# EMG_FSR.net
KiCad netlist of a schematic drawn in EAGLE
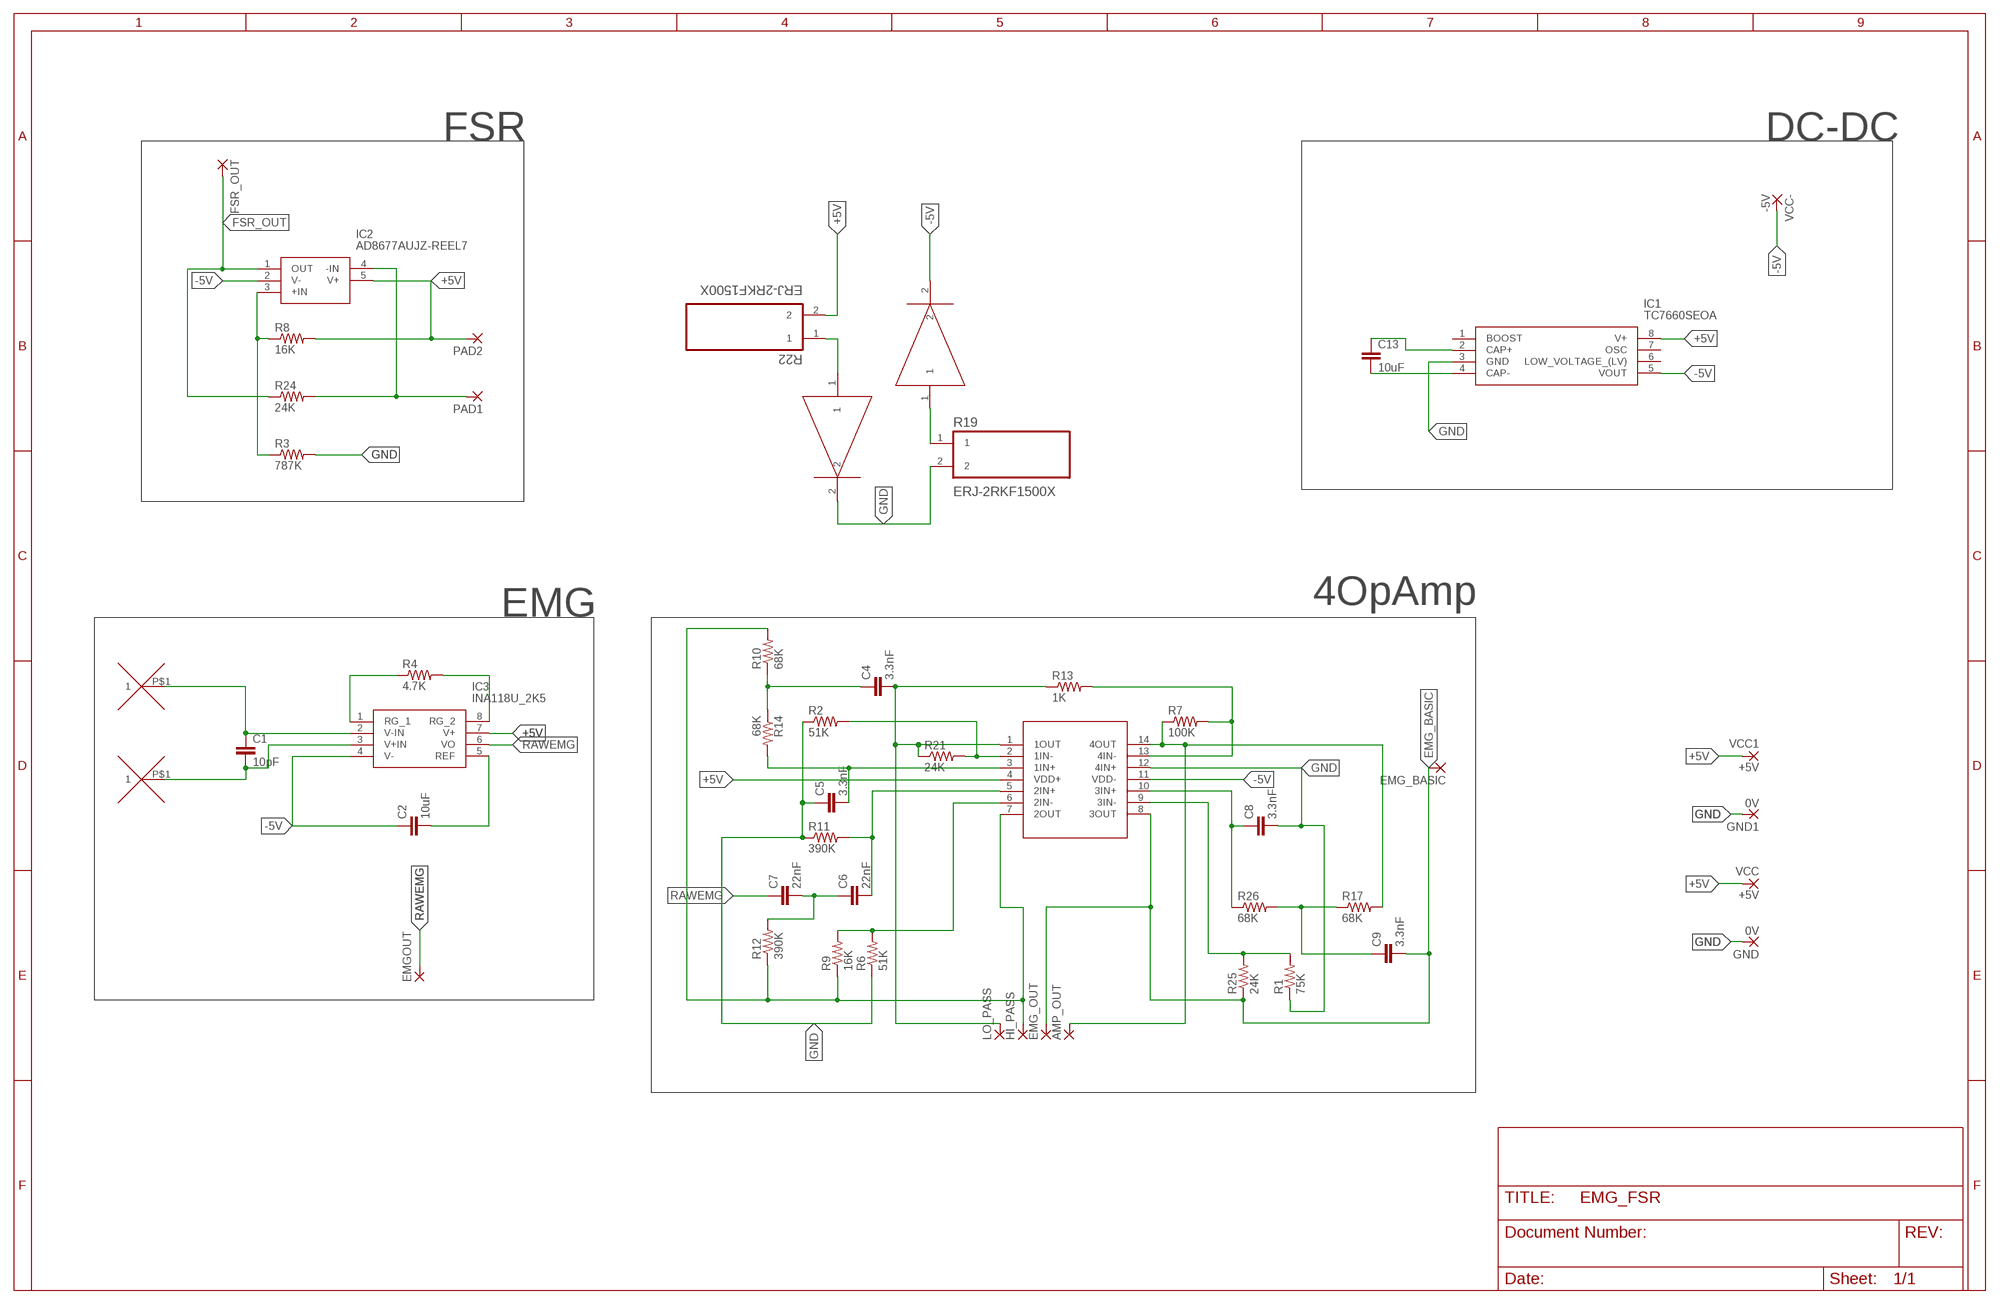
[diagram p0: schematic, sheet 1]

(export (version "E")
  (design (tool "Eeschema 10.0.6"))
  (components
    (comp (ref "AMP_OUT")
      (value "1,6/0,8")
      (footprint "eagle-import:1,6_0,8")
      (libsource (lib "eagle-import") (part "1,6/0,8"))
    )
    (comp (ref "C1")
      (value "10pF")
      (footprint "eagle-import:HPC0201")
      (libsource (lib "eagle-import") (part "rcl@1_C-EUHPC0201"))
    )
    (comp (ref "C2")
      (value "10uF")
      (footprint "eagle-import:C0805")
      (libsource (lib "eagle-import") (part "rcl@1_C-EUC0805"))
    )
    (comp (ref "C4")
      (value "3.3nF")
      (footprint "eagle-import:C1206")
      (libsource (lib "eagle-import") (part "C-EUC1206"))
    )
    (comp (ref "C5")
      (value "3.3nF")
      (footprint "eagle-import:C1206")
      (libsource (lib "eagle-import") (part "C-EUC1206"))
    )
    (comp (ref "C6")
      (value "22nF")
      (footprint "eagle-import:C0805")
      (libsource (lib "eagle-import") (part "C-EUC0805"))
    )
    (comp (ref "C7")
      (value "22nF")
      (footprint "eagle-import:C0805")
      (libsource (lib "eagle-import") (part "C-EUC0805"))
    )
    (comp (ref "C8")
      (value "3.3nF")
      (footprint "eagle-import:C1206")
      (libsource (lib "eagle-import") (part "C-EUC1206"))
    )
    (comp (ref "C9")
      (value "3.3nF")
      (footprint "eagle-import:C1206")
      (libsource (lib "eagle-import") (part "C-EUC1206"))
    )
    (comp (ref "C13")
      (value "10uF")
      (footprint "eagle-import:C0805K")
      (libsource (lib "eagle-import") (part "rcl@1_C-EUC0805K"))
    )
    (comp (ref "EMGOUT")
      (value "1,6/0,8")
      (footprint "eagle-import:1,6_0,8")
      (libsource (lib "eagle-import") (part "1,6/0,8"))
    )
    (comp (ref "EMG_BASIC")
      (value "1,6/0,8")
      (footprint "eagle-import:1,6_0,8")
      (libsource (lib "eagle-import") (part "1,6/0,8"))
    )
    (comp (ref "EMG_OUT")
      (value "1,6/0,8")
      (footprint "eagle-import:1,6_0,8")
      (libsource (lib "eagle-import") (part "1,6/0,8"))
    )
    (comp (ref "FSR_OUT")
      (value "1,6/0,8")
      (footprint "eagle-import:1,6_0,8")
      (libsource (lib "eagle-import") (part "1,6/0,8"))
    )
    (comp (ref "GND")
      (value "0V")
      (footprint "eagle-import:1,6_0,8")
      (libsource (lib "eagle-import") (part "1,6/0,8"))
    )
    (comp (ref "GND1")
      (value "0V")
      (footprint "eagle-import:1,6_0,8")
      (libsource (lib "eagle-import") (part "1,6/0,8"))
    )
    (comp (ref "HI_PASS")
      (value "1,6/0,8")
      (footprint "eagle-import:1,6_0,8")
      (libsource (lib "eagle-import") (part "1,6/0,8"))
    )
    (comp (ref "IC1")
      (value "TC7660SEOA")
      (footprint "eagle-import:SOIC127P600X175-8N")
      (fields (field (name "MOUSER_PART_NUMBER") "579-TC7660SEOA"))
      (libsource (lib "eagle-import") (part "TC7660SEOA"))
    )
    (comp (ref "IC2")
      (value "AD8677AUJZ-REEL7")
      (footprint "eagle-import:SOT95P280X100-5N")
      (fields (field (name "MOUSER_PART_NUMBER") "584-AD8677AUJZ-R7"))
      (libsource (lib "eagle-import") (part "AD8677AUJZ-REEL7"))
    )
    (comp (ref "IC3")
      (value "INA118U_2K5")
      (footprint "eagle-import:SOIC127P600X175-8N")
      (fields
        (field (name "ARROW_PART_NUMBER") "INA118U/2K5")
        (field (name "MOUSER_PART_NUMBER") "595-INA118U/2K5")
      )
      (libsource (lib "eagle-import") (part "INA118U_2K5"))
    )
    (comp (ref "LO_PASS")
      (value "1,6/0,8")
      (footprint "eagle-import:1,6_0,8")
      (libsource (lib "eagle-import") (part "1,6/0,8"))
    )
    (comp (ref "PAD1")
      (value "SMD2")
      (footprint "eagle-import:SMD1,27-2,54")
      (libsource (lib "eagle-import") (part "SMD2"))
    )
    (comp (ref "PAD2")
      (value "SMD2")
      (footprint "eagle-import:SMD1,27-2,54")
      (libsource (lib "eagle-import") (part "SMD2"))
    )
    (comp (ref "R1")
      (value "75K")
      (footprint "eagle-import:R0402")
      (libsource (lib "eagle-import") (part "adafruit@2_R-US_R0402"))
    )
    (comp (ref "R2")
      (value "51K")
      (footprint "eagle-import:R0402")
      (libsource (lib "eagle-import") (part "adafruit@2_R-US_R0402"))
    )
    (comp (ref "R3")
      (value "787K")
      (footprint "eagle-import:R0805")
      (libsource (lib "eagle-import") (part "rcl_R-US_R0805"))
    )
    (comp (ref "R4")
      (value "4.7K")
      (footprint "eagle-import:R0402")
      (libsource (lib "eagle-import") (part "adafruit@1_R-US_R0402"))
    )
    (comp (ref "R6")
      (value "51K")
      (footprint "eagle-import:R0402")
      (libsource (lib "eagle-import") (part "adafruit@2_R-US_R0402"))
    )
    (comp (ref "R7")
      (value "100K")
      (footprint "eagle-import:R1005")
      (libsource (lib "eagle-import") (part "adafruit@1_R-US_R1005"))
    )
    (comp (ref "R8")
      (value "16K")
      (footprint "eagle-import:R0402")
      (libsource (lib "eagle-import") (part "adafruit@2_R-US_R0402"))
    )
    (comp (ref "R9")
      (value "16K")
      (footprint "eagle-import:R0402")
      (libsource (lib "eagle-import") (part "adafruit@2_R-US_R0402"))
    )
    (comp (ref "R10")
      (value "68K")
      (footprint "eagle-import:R0402")
      (libsource (lib "eagle-import") (part "adafruit@2_R-US_R0402"))
    )
    (comp (ref "R11")
      (value "390K")
      (footprint "eagle-import:R0603")
      (libsource (lib "eagle-import") (part "R-US_R0603"))
    )
    (comp (ref "R12")
      (value "390K")
      (footprint "eagle-import:R0603")
      (libsource (lib "eagle-import") (part "adafruit@1_R-US_R0603"))
    )
    (comp (ref "R13")
      (value "1K")
      (footprint "eagle-import:R0402")
      (libsource (lib "eagle-import") (part "adafruit@2_R-US_R0402"))
    )
    (comp (ref "R14")
      (value "68K")
      (footprint "eagle-import:R0402")
      (libsource (lib "eagle-import") (part "adafruit@2_R-US_R0402"))
    )
    (comp (ref "R17")
      (value "68K")
      (footprint "eagle-import:R0402")
      (libsource (lib "eagle-import") (part "adafruit@2_R-US_R0402"))
    )
    (comp (ref "R19")
      (value "ERJ-2RKF1500X")
      (footprint "eagle-import:RESC1005X40N")
      (fields (field (name "DIGI-KEY_PART_NUMBER") "P150LCT-ND") (field (name "MF") "Panasonic Electronic"))
      (libsource (lib "eagle-import") (part "ERJ-2RKF1500X"))
    )
    (comp (ref "R20")
      (value "RESC0402X40N")
      (footprint "eagle-import:RESC0402X40N")
      (fields (field (name "MANUFACTURER") "KOA"))
      (libsource (lib "eagle-import") (part "RESC0402X40N"))
    )
    (comp (ref "R21")
      (value "24K")
      (footprint "eagle-import:R0402")
      (libsource (lib "eagle-import") (part "adafruit@2_R-US_R0402"))
    )
    (comp (ref "R22")
      (value "ERJ-2RKF1500X")
      (footprint "eagle-import:RESC1005X40N")
      (fields (field (name "DIGI-KEY_PART_NUMBER") "P150LCT-ND") (field (name "MF") "Panasonic Electronic"))
      (libsource (lib "eagle-import") (part "ERJ-2RKF1500X"))
    )
    (comp (ref "R24")
      (value "24K")
      (footprint "eagle-import:R0402")
      (libsource (lib "eagle-import") (part "adafruit@2_R-US_R0402"))
    )
    (comp (ref "R25")
      (value "24K")
      (footprint "eagle-import:R0402")
      (libsource (lib "eagle-import") (part "adafruit@2_R-US_R0402"))
    )
    (comp (ref "R26")
      (value "68K")
      (footprint "eagle-import:R0402")
      (libsource (lib "eagle-import") (part "adafruit@2_R-US_R0402"))
    )
    (comp (ref "RED")
      (value "RESC0402X40N")
      (footprint "eagle-import:RESC0402X40N")
      (fields (field (name "MANUFACTURER") "KOA"))
      (libsource (lib "eagle-import") (part "RESC0402X40N"))
    )
    (comp (ref "U$1")
      (value "TLC2274-HT")
      (footprint "eagle-import:SOP65P640X120-14N")
      (libsource (lib "eagle-import") (part "TLC2274-HT"))
    )
    (comp (ref "U$2")
      (value "EMG_VIA")
      (footprint "eagle-import:EMG_VIA")
      (libsource (lib "eagle-import") (part "EMG_VIA"))
    )
    (comp (ref "U$3")
      (value "EMG_VIA")
      (footprint "eagle-import:EMG_VIA")
      (libsource (lib "eagle-import") (part "EMG_VIA"))
    )
    (comp (ref "VCC")
      (value "+5V")
      (footprint "eagle-import:1,6_0,8")
      (libsource (lib "eagle-import") (part "1,6/0,8"))
    )
    (comp (ref "VCC-")
      (value "-5V")
      (footprint "eagle-import:1,6_0,8")
      (libsource (lib "eagle-import") (part "1,6/0,8"))
    )
    (comp (ref "VCC1")
      (value "+5V")
      (footprint "eagle-import:1,6_0,8")
      (libsource (lib "eagle-import") (part "1,6/0,8"))
    )
  )
  (nets
    (net (code "1") (name "+5V") (class "Default")
      (node (ref "IC1") (pin "8") (pinfunction "V+_8") (pintype "bidirectional"))
      (node (ref "IC2") (pin "5") (pinfunction "V+_5") (pintype "bidirectional"))
      (node (ref "IC3") (pin "7") (pinfunction "V+_7") (pintype "bidirectional"))
      (node (ref "PAD2") (pin "1") (pinfunction "P_1") (pintype "passive"))
      (node (ref "R22") (pin "2") (pinfunction "2_2") (pintype "bidirectional"))
      (node (ref "R8") (pin "2") (pinfunction "2_2") (pintype "passive"))
      (node (ref "U$1") (pin "4") (pinfunction "VDD+_4") (pintype "bidirectional"))
      (node (ref "VCC") (pin "1") (pinfunction "P_1") (pintype "passive"))
      (node (ref "VCC1") (pin "1") (pinfunction "P_1") (pintype "passive"))
    )
    (net (code "2") (name "-5V") (class "Default")
      (node (ref "C2") (pin "1") (pinfunction "1_1") (pintype "passive"))
      (node (ref "IC1") (pin "5") (pinfunction "VOUT_5") (pintype "bidirectional"))
      (node (ref "IC2") (pin "2") (pinfunction "V-_2") (pintype "bidirectional"))
      (node (ref "IC3") (pin "4") (pinfunction "V-_4") (pintype "bidirectional"))
      (node (ref "R20") (pin "2") (pinfunction "2_2") (pintype "bidirectional"))
      (node (ref "U$1") (pin "11") (pinfunction "VDD-_11") (pintype "bidirectional"))
      (node (ref "VCC-") (pin "1") (pinfunction "P_1") (pintype "passive"))
    )
    (net (code "3") (name "EMG_BASIC") (class "Default")
      (node (ref "C9") (pin "2") (pinfunction "2_2") (pintype "passive"))
      (node (ref "EMG_BASIC") (pin "1") (pinfunction "P_1") (pintype "passive"))
      (node (ref "EMG_OUT") (pin "1") (pinfunction "P_1") (pintype "passive"))
      (node (ref "R25") (pin "1") (pinfunction "1_1") (pintype "passive"))
      (node (ref "U$1") (pin "8") (pinfunction "3OUT_8") (pintype "bidirectional"))
    )
    (net (code "4") (name "FSR_OUT") (class "Default")
      (node (ref "FSR_OUT") (pin "1") (pinfunction "P_1") (pintype "passive"))
      (node (ref "IC2") (pin "1") (pinfunction "OUT_1") (pintype "output"))
      (node (ref "R24") (pin "1") (pinfunction "1_1") (pintype "passive"))
    )
    (net (code "5") (name "GND") (class "Default")
      (node (ref "C5") (pin "1") (pinfunction "1_1") (pintype "passive"))
      (node (ref "C8") (pin "2") (pinfunction "2_2") (pintype "passive"))
      (node (ref "GND") (pin "1") (pinfunction "P_1") (pintype "passive"))
      (node (ref "GND1") (pin "1") (pinfunction "P_1") (pintype "passive"))
      (node (ref "IC1") (pin "3") (pinfunction "GND_3") (pintype "bidirectional"))
      (node (ref "R1") (pin "1") (pinfunction "1_1") (pintype "passive"))
      (node (ref "R11") (pin "1") (pinfunction "1_1") (pintype "passive"))
      (node (ref "R19") (pin "2") (pinfunction "2_2") (pintype "bidirectional"))
      (node (ref "R2") (pin "1") (pinfunction "1_1") (pintype "passive"))
      (node (ref "R3") (pin "2") (pinfunction "2_2") (pintype "passive"))
      (node (ref "R6") (pin "1") (pinfunction "1_1") (pintype "passive"))
      (node (ref "RED") (pin "2") (pinfunction "2_2") (pintype "bidirectional"))
      (node (ref "U$1") (pin "12") (pinfunction "4IN+_12") (pintype "bidirectional"))
    )
    (net (code "6") (name "Net-(AMP_OUT-P)") (class "Default")
      (node (ref "AMP_OUT") (pin "1") (pinfunction "P_1") (pintype "passive"))
      (node (ref "R17") (pin "2") (pinfunction "2_2") (pintype "passive"))
      (node (ref "R7") (pin "1") (pinfunction "1_1") (pintype "passive"))
      (node (ref "U$1") (pin "14") (pinfunction "4OUT_14") (pintype "bidirectional"))
    )
    (net (code "7") (name "Net-(C4-Pad1)") (class "Default")
      (node (ref "C4") (pin "1") (pinfunction "1_1") (pintype "passive"))
      (node (ref "R10") (pin "1") (pinfunction "1_1") (pintype "passive"))
      (node (ref "R14") (pin "1") (pinfunction "1_1") (pintype "passive"))
    )
    (net (code "8") (name "Net-(C6-Pad1)") (class "Default")
      (node (ref "C6") (pin "1") (pinfunction "1_1") (pintype "passive"))
      (node (ref "C7") (pin "2") (pinfunction "2_2") (pintype "passive"))
      (node (ref "R12") (pin "2") (pinfunction "2_2") (pintype "passive"))
    )
    (net (code "9") (name "Net-(C9-Pad1)") (class "Default")
      (node (ref "C9") (pin "1") (pinfunction "1_1") (pintype "passive"))
      (node (ref "R17") (pin "1") (pinfunction "1_1") (pintype "passive"))
      (node (ref "R26") (pin "2") (pinfunction "2_2") (pintype "passive"))
    )
    (net (code "10") (name "Net-(HI_PASS-P)") (class "Default")
      (node (ref "HI_PASS") (pin "1") (pinfunction "P_1") (pintype "passive"))
      (node (ref "R10") (pin "2") (pinfunction "2_2") (pintype "passive"))
      (node (ref "R12") (pin "1") (pinfunction "1_1") (pintype "passive"))
      (node (ref "R9") (pin "1") (pinfunction "1_1") (pintype "passive"))
      (node (ref "U$1") (pin "7") (pinfunction "2OUT_7") (pintype "bidirectional"))
    )
    (net (code "11") (name "Net-(IC1-CAP+)") (class "Default")
      (node (ref "C13") (pin "1") (pinfunction "1_1") (pintype "passive"))
      (node (ref "IC1") (pin "2") (pinfunction "CAP+_2") (pintype "bidirectional"))
    )
    (net (code "12") (name "Net-(IC1-CAP-)") (class "Default")
      (node (ref "C13") (pin "2") (pinfunction "2_2") (pintype "passive"))
      (node (ref "IC1") (pin "4") (pinfunction "CAP-_4") (pintype "bidirectional"))
    )
    (net (code "13") (name "Net-(IC2-+IN)") (class "Default")
      (node (ref "IC2") (pin "3") (pinfunction "+IN_3") (pintype "input"))
      (node (ref "R3") (pin "1") (pinfunction "1_1") (pintype "passive"))
      (node (ref "R8") (pin "1") (pinfunction "1_1") (pintype "passive"))
    )
    (net (code "14") (name "Net-(IC2--IN)") (class "Default")
      (node (ref "IC2") (pin "4") (pinfunction "-IN_4") (pintype "input"))
      (node (ref "PAD1") (pin "1") (pinfunction "P_1") (pintype "passive"))
      (node (ref "R24") (pin "2") (pinfunction "2_2") (pintype "passive"))
    )
    (net (code "15") (name "Net-(IC3-REF)") (class "Default")
      (node (ref "C2") (pin "2") (pinfunction "2_2") (pintype "passive"))
      (node (ref "IC3") (pin "5") (pinfunction "REF_5") (pintype "bidirectional"))
    )
    (net (code "16") (name "Net-(IC3-RG_1)") (class "Default")
      (node (ref "IC3") (pin "1") (pinfunction "RG_1_1") (pintype "bidirectional"))
      (node (ref "R4") (pin "1") (pinfunction "1_1") (pintype "passive"))
    )
    (net (code "17") (name "Net-(IC3-RG_2)") (class "Default")
      (node (ref "IC3") (pin "8") (pinfunction "RG_2_8") (pintype "bidirectional"))
      (node (ref "R4") (pin "2") (pinfunction "2_2") (pintype "passive"))
    )
    (net (code "18") (name "Net-(IC3-V+IN)") (class "Default")
      (node (ref "C1") (pin "2") (pinfunction "2_2") (pintype "passive"))
      (node (ref "IC3") (pin "3") (pinfunction "V+IN_3") (pintype "bidirectional"))
      (node (ref "U$3") (pin "P$1") (pinfunction "1_P$1") (pintype "bidirectional"))
    )
    (net (code "19") (name "Net-(IC3-V-IN)") (class "Default")
      (node (ref "C1") (pin "1") (pinfunction "1_1") (pintype "passive"))
      (node (ref "IC3") (pin "2") (pinfunction "V-IN_2") (pintype "bidirectional"))
      (node (ref "U$2") (pin "P$1") (pinfunction "1_P$1") (pintype "bidirectional"))
    )
    (net (code "20") (name "Net-(LO_PASS-P)") (class "Default")
      (node (ref "C4") (pin "2") (pinfunction "2_2") (pintype "passive"))
      (node (ref "LO_PASS") (pin "1") (pinfunction "P_1") (pintype "passive"))
      (node (ref "R13") (pin "1") (pinfunction "1_1") (pintype "passive"))
      (node (ref "R21") (pin "1") (pinfunction "1_1") (pintype "passive"))
      (node (ref "U$1") (pin "1") (pinfunction "1OUT_1") (pintype "bidirectional"))
    )
    (net (code "21") (name "Net-(R19-Pad1)") (class "Default")
      (node (ref "R19") (pin "1") (pinfunction "1_1") (pintype "bidirectional"))
      (node (ref "R20") (pin "1") (pinfunction "1_1") (pintype "bidirectional"))
    )
    (net (code "22") (name "Net-(R22-Pad1)") (class "Default")
      (node (ref "R22") (pin "1") (pinfunction "1_1") (pintype "bidirectional"))
      (node (ref "RED") (pin "1") (pinfunction "1_1") (pintype "bidirectional"))
    )
    (net (code "23") (name "Net-(U$1-1IN+)") (class "Default")
      (node (ref "C5") (pin "2") (pinfunction "2_2") (pintype "passive"))
      (node (ref "R14") (pin "2") (pinfunction "2_2") (pintype "passive"))
      (node (ref "U$1") (pin "3") (pinfunction "1IN+_3") (pintype "bidirectional"))
    )
    (net (code "24") (name "Net-(U$1-1IN-)") (class "Default")
      (node (ref "R2") (pin "2") (pinfunction "2_2") (pintype "passive"))
      (node (ref "R21") (pin "2") (pinfunction "2_2") (pintype "passive"))
      (node (ref "U$1") (pin "2") (pinfunction "1IN-_2") (pintype "bidirectional"))
    )
    (net (code "25") (name "Net-(U$1-2IN+)") (class "Default")
      (node (ref "C6") (pin "2") (pinfunction "2_2") (pintype "passive"))
      (node (ref "R11") (pin "2") (pinfunction "2_2") (pintype "passive"))
      (node (ref "U$1") (pin "5") (pinfunction "2IN+_5") (pintype "bidirectional"))
    )
    (net (code "26") (name "Net-(U$1-2IN-)") (class "Default")
      (node (ref "R6") (pin "2") (pinfunction "2_2") (pintype "passive"))
      (node (ref "R9") (pin "2") (pinfunction "2_2") (pintype "passive"))
      (node (ref "U$1") (pin "6") (pinfunction "2IN-_6") (pintype "bidirectional"))
    )
    (net (code "27") (name "Net-(U$1-3IN+)") (class "Default")
      (node (ref "C8") (pin "1") (pinfunction "1_1") (pintype "passive"))
      (node (ref "R26") (pin "1") (pinfunction "1_1") (pintype "passive"))
      (node (ref "U$1") (pin "10") (pinfunction "3IN+_10") (pintype "bidirectional"))
    )
    (net (code "28") (name "Net-(U$1-3IN-)") (class "Default")
      (node (ref "R1") (pin "2") (pinfunction "2_2") (pintype "passive"))
      (node (ref "R25") (pin "2") (pinfunction "2_2") (pintype "passive"))
      (node (ref "U$1") (pin "9") (pinfunction "3IN-_9") (pintype "bidirectional"))
    )
    (net (code "29") (name "Net-(U$1-4IN-)") (class "Default")
      (node (ref "R13") (pin "2") (pinfunction "2_2") (pintype "passive"))
      (node (ref "R7") (pin "2") (pinfunction "2_2") (pintype "passive"))
      (node (ref "U$1") (pin "13") (pinfunction "4IN-_13") (pintype "bidirectional"))
    )
    (net (code "30") (name "RAWEMG") (class "Default")
      (node (ref "C7") (pin "1") (pinfunction "1_1") (pintype "passive"))
      (node (ref "EMGOUT") (pin "1") (pinfunction "P_1") (pintype "passive"))
      (node (ref "IC3") (pin "6") (pinfunction "VO_6") (pintype "bidirectional"))
    )
    (net (code "31") (name "unconnected-(IC1-BOOST-Pad1)") (class "Default")
      (node (ref "IC1") (pin "1") (pinfunction "BOOST_1") (pintype "bidirectional"))
    )
    (net (code "32") (name "unconnected-(IC1-LOW_VOLTAGE_(LV)-Pad6)") (class "Default")
      (node (ref "IC1") (pin "6") (pinfunction "LOW_VOLTAGE_(LV)_6") (pintype "bidirectional"))
    )
    (net (code "33") (name "unconnected-(IC1-OSC-Pad7)") (class "Default")
      (node (ref "IC1") (pin "7") (pinfunction "OSC_7") (pintype "bidirectional"))
    )
  )
)
